# 408_jetracer_ledappend_board.net
KiCad netlist of a schematic drawn in EAGLE
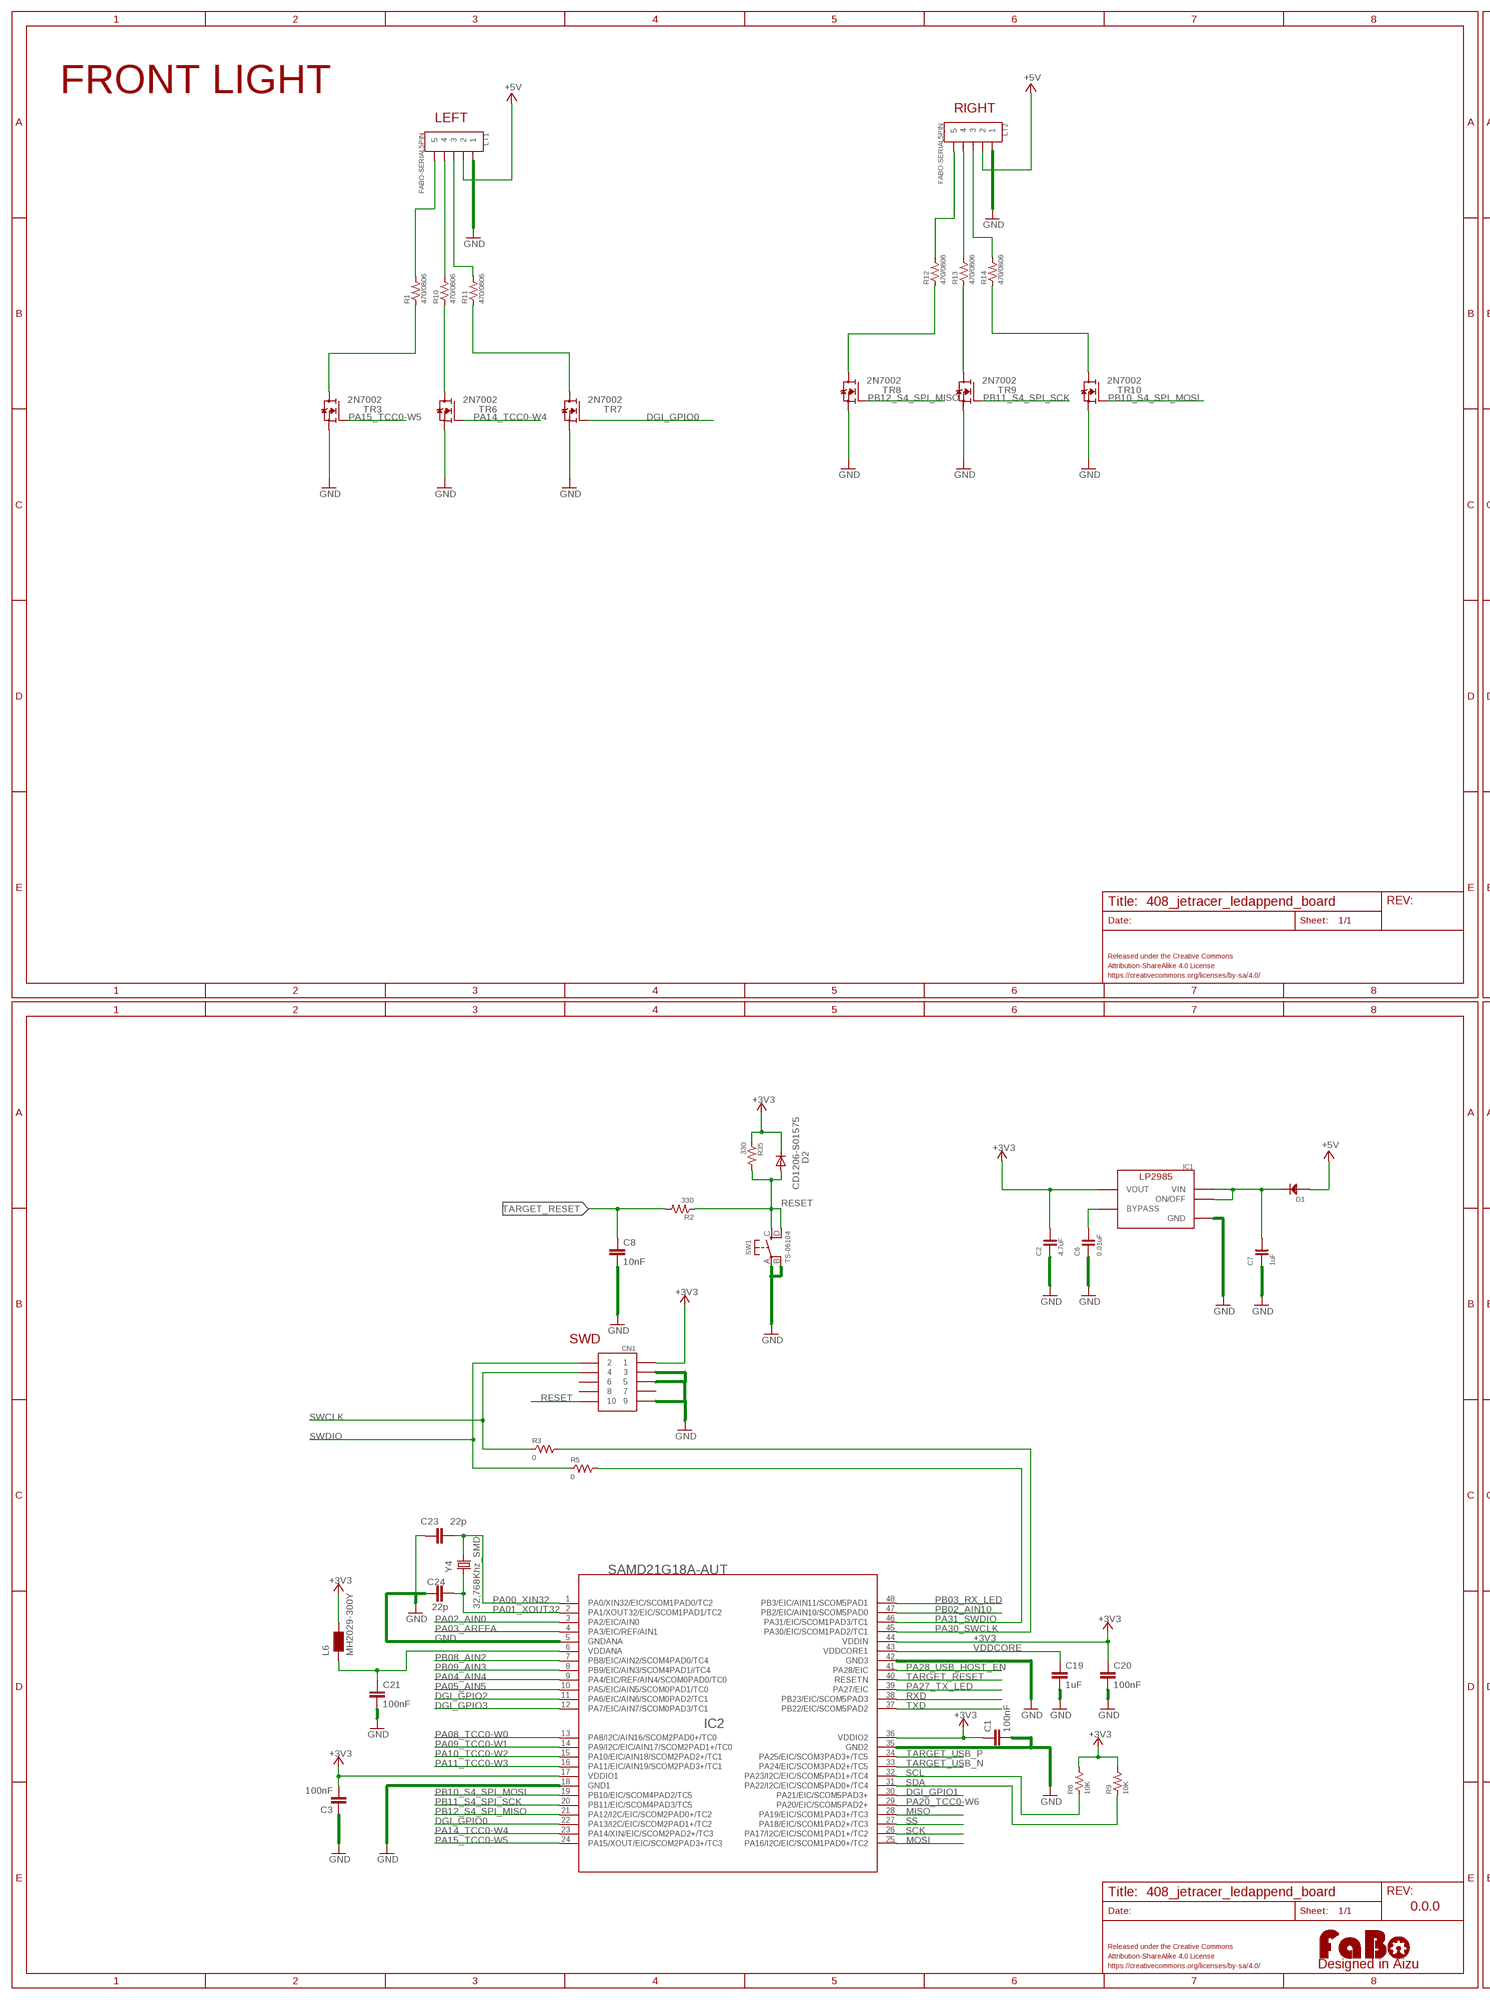
[diagram p0: schematic, sheet 1, part 1 of 2]
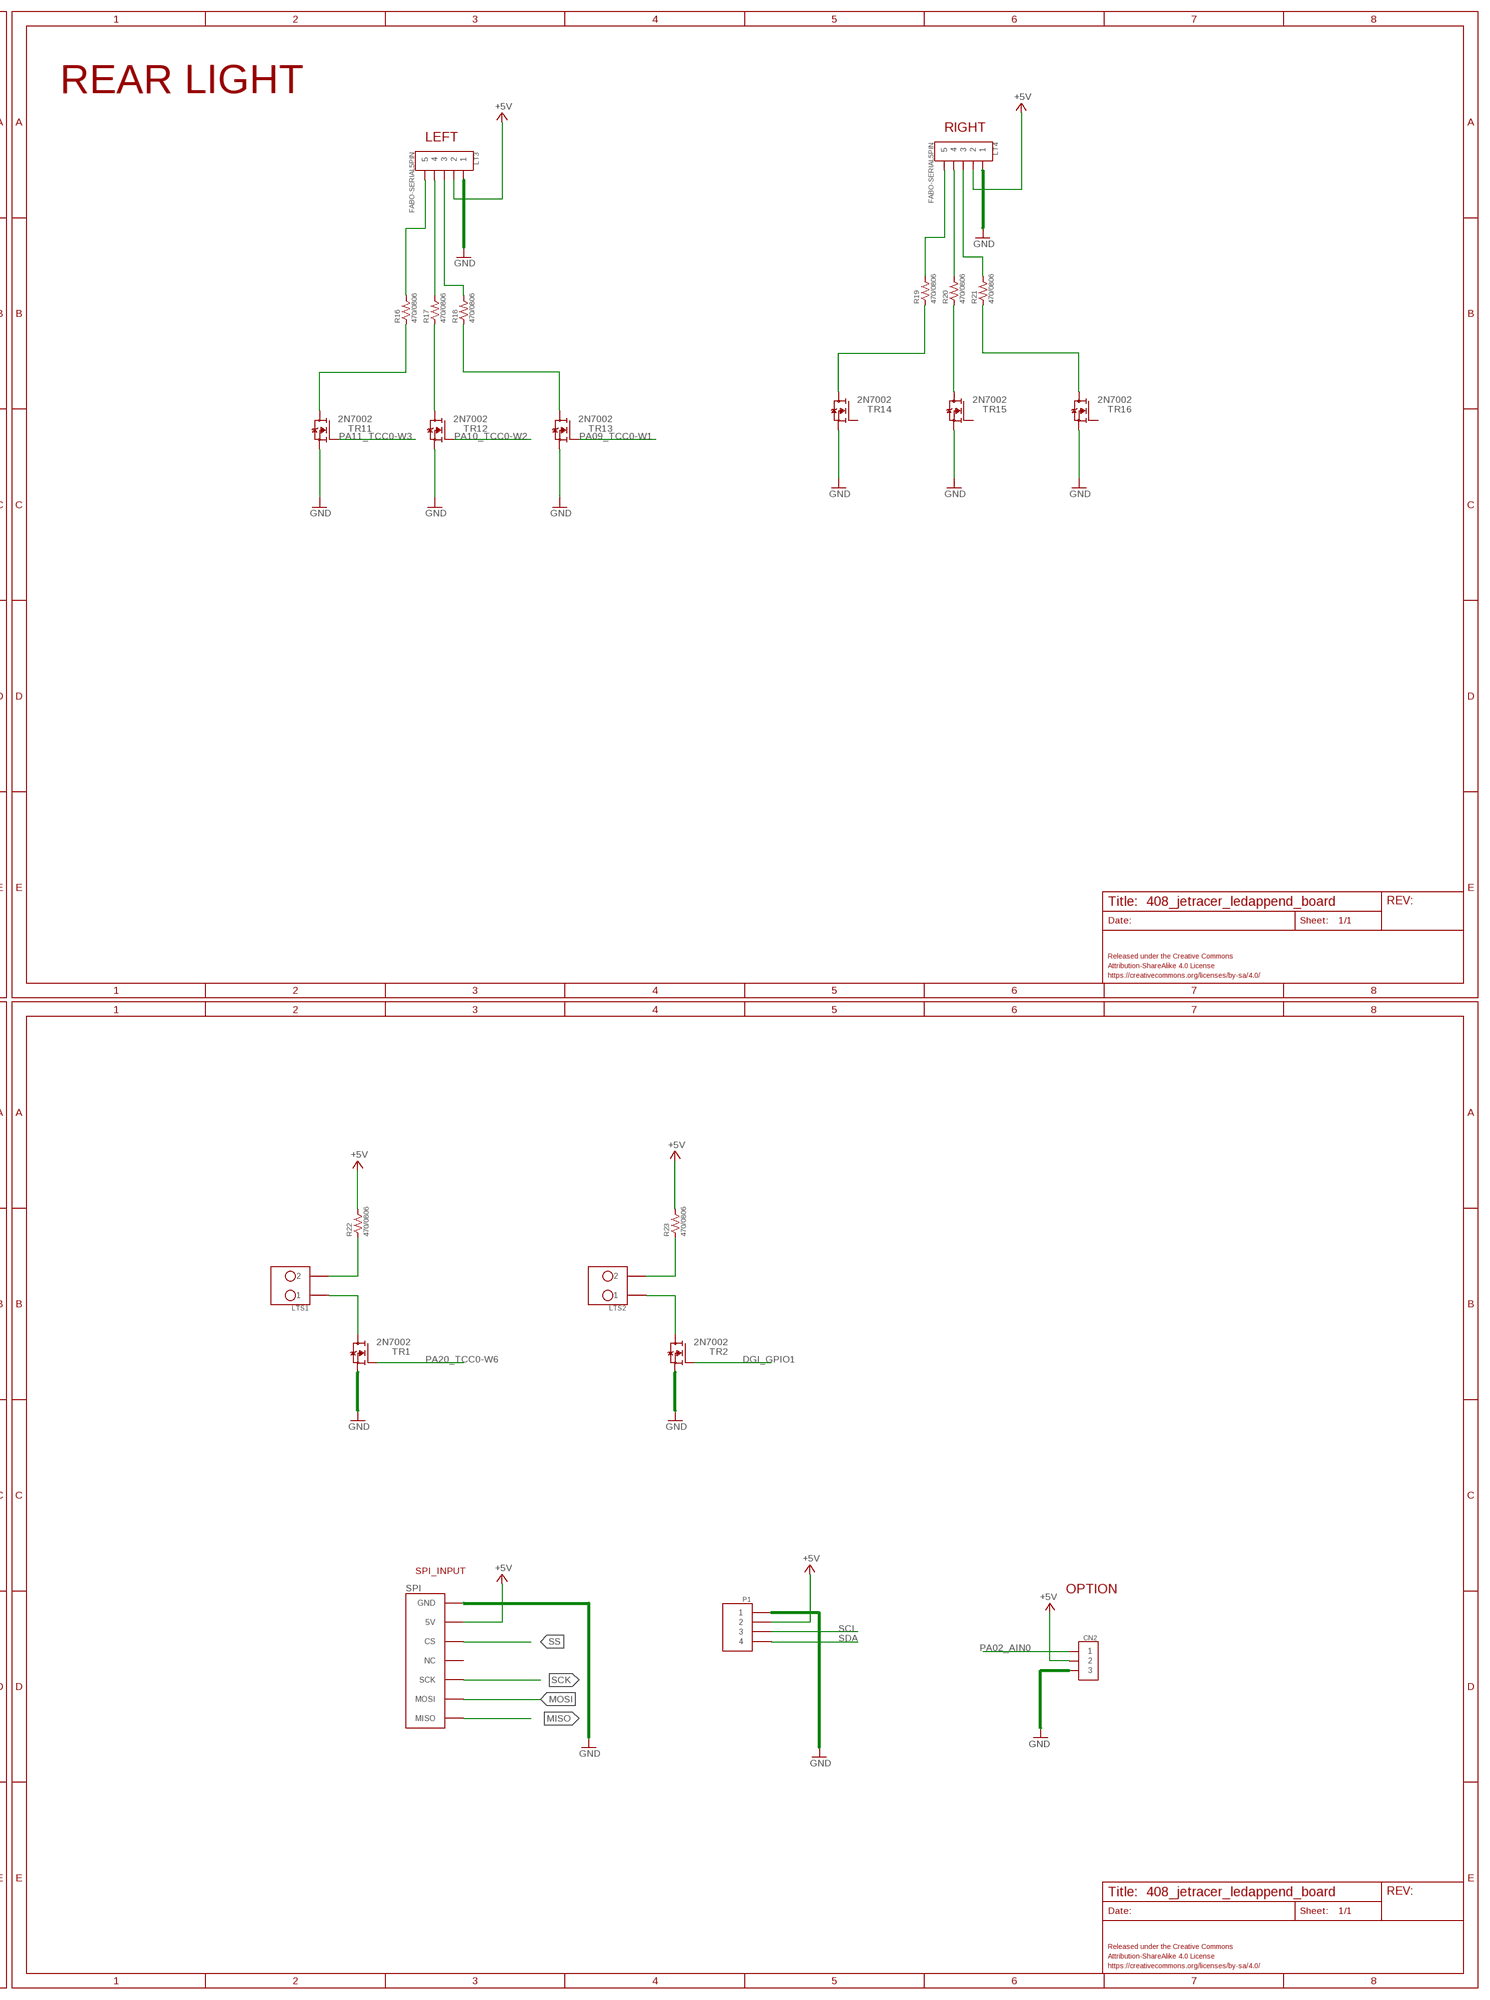
[diagram p1: schematic, sheet 1, part 2 of 2]

(export (version "E")
  (design (tool "Eeschema 10.0.6"))
  (components
    (comp (ref "C1")
      (value "100nF")
      (footprint "eagle-import:C0603-ROUND")
      (fields (field (name "PART_NUMBER") "cl10b104kbnc"))
      (libsource (lib "eagle-import") (part "0015_100NF_0603"))
    )
    (comp (ref "C2")
      (value "4.7uF")
      (footprint "eagle-import:0603")
      (libsource (lib "eagle-import") (part "CAPACITOR-0603"))
    )
    (comp (ref "C3")
      (value "100nF")
      (footprint "eagle-import:C0603-ROUND")
      (fields (field (name "PART_NUMBER") "cl10b104kbnc"))
      (libsource (lib "eagle-import") (part "0015_100NF_0603"))
    )
    (comp (ref "C6")
      (value "0.01uF")
      (footprint "eagle-import:0603")
      (libsource (lib "eagle-import") (part "CAPACITOR-0603"))
    )
    (comp (ref "C7")
      (value "1uF")
      (footprint "eagle-import:0603")
      (libsource (lib "eagle-import") (part "CAPACITOR-0603"))
    )
    (comp (ref "C8")
      (value "10nF")
      (footprint "eagle-import:C0603-ROUND")
      (fields (field (name "PART_NUMBER") "10nF_0603"))
      (libsource (lib "eagle-import") (part "0142_10NF_0603"))
    )
    (comp (ref "C19")
      (value "1uF")
      (footprint "eagle-import:C0603-ROUND")
      (fields (field (name "PART_NUMBER") "1uF_0603/GRM188R61E105KA12D"))
      (libsource (lib "eagle-import") (part "0006_1UF_0603/GRM188R61E105KA12D"))
    )
    (comp (ref "C20")
      (value "100nF")
      (footprint "eagle-import:C0603-ROUND")
      (fields (field (name "PART_NUMBER") "cl10b104kbnc"))
      (libsource (lib "eagle-import") (part "0015_100NF_0603"))
    )
    (comp (ref "C21")
      (value "100nF")
      (footprint "eagle-import:C0603-ROUND")
      (fields (field (name "PART_NUMBER") "cl10b104kbnc"))
      (libsource (lib "eagle-import") (part "0015_100NF_0603"))
    )
    (comp (ref "C23")
      (value "22p")
      (footprint "eagle-import:C0603-ROUND")
      (fields (field (name "PART_NUMBER") "22pF_0603"))
      (libsource (lib "eagle-import") (part "0014_22PF_0603"))
    )
    (comp (ref "C24")
      (value "22p")
      (footprint "eagle-import:C0603-ROUND")
      (fields (field (name "PART_NUMBER") "22pF_0603"))
      (libsource (lib "eagle-import") (part "0014_22PF_0603"))
    )
    (comp (ref "CN1")
      (value "PIN-HEADER-SMT(1.27MM)2X5")
      (footprint "eagle-import:PIN-HEADER-SMT(1.27MM)2X5")
      (libsource (lib "eagle-import") (part "PIN-HEADER-SMT(1.27MM)2X5"))
    )
    (comp (ref "CN2")
      (value "PIN_1X3")
      (footprint "eagle-import:PIN_1X3")
      (libsource (lib "eagle-import") (part "PIN_1X3"))
    )
    (comp (ref "D1")
      (value "DIODE-SOD-323")
      (footprint "eagle-import:SOD-323")
      (libsource (lib "eagle-import") (part "DIODE-SOD-323"))
    )
    (comp (ref "D2")
      (value "CD1206-S01575")
      (footprint "eagle-import:MINIMELF")
      (libsource (lib "eagle-import") (part "0012_CD1206-S01575"))
    )
    (comp (ref "IC1")
      (value "LP2985-33DBV")
      (footprint "eagle-import:SOT-23-5")
      (libsource (lib "eagle-import") (part "LP2985-33DBV"))
    )
    (comp (ref "IC2")
      (value "SAMD21G18A-AUT")
      (footprint "eagle-import:TQFP48-7X7")
      (libsource (lib "eagle-import") (part "1792_SAMD21G18A-AUT"))
    )
    (comp (ref "L6")
      (value "MH2029-300Y")
      (footprint "eagle-import:0805")
      (fields (field (name "PART_NUMBER") "BLM21PG300SN1D_/_MH2029-300Y"))
      (libsource (lib "eagle-import") (part "0001_BLM21PG300SN1D_/_MH2029-300Y"))
    )
    (comp (ref "LOGO2")
      (value "LOGO_FABO-M_BOTTOM")
      (footprint "eagle-import:LOGO_FABO_M_BOTTOM")
      (libsource (lib "eagle-import") (part "LOGO_FABO-M_BOTTOM"))
    )
    (comp (ref "LT1")
      (value "FABO-SERIAL5PIN")
      (footprint "eagle-import:BM05B-PASS-1")
      (libsource (lib "eagle-import") (part "FABO-SERIAL5PIN"))
    )
    (comp (ref "LT2")
      (value "FABO-SERIAL5PIN")
      (footprint "eagle-import:BM05B-PASS-1")
      (libsource (lib "eagle-import") (part "FABO-SERIAL5PIN"))
    )
    (comp (ref "LT3")
      (value "FABO-SERIAL5PIN")
      (footprint "eagle-import:BM05B-PASS-1")
      (libsource (lib "eagle-import") (part "FABO-SERIAL5PIN"))
    )
    (comp (ref "LT4")
      (value "FABO-SERIAL5PIN")
      (footprint "eagle-import:BM05B-PASS-1")
      (libsource (lib "eagle-import") (part "FABO-SERIAL5PIN"))
    )
    (comp (ref "LTS1")
      (value "B2B-XH-AM")
      (footprint "eagle-import:B2B-XH-AM")
      (libsource (lib "eagle-import") (part "B2B-XH-AM"))
    )
    (comp (ref "LTS2")
      (value "B2B-XH-AM")
      (footprint "eagle-import:B2B-XH-AM")
      (libsource (lib "eagle-import") (part "B2B-XH-AM"))
    )
    (comp (ref "P1")
      (value "4PIN_HEADER_1.25MM")
      (footprint "eagle-import:4PIN_1.25MM")
      (libsource (lib "eagle-import") (part "4PIN_HEADER_1.25MM"))
    )
    (comp (ref "R1")
      (value "470/0806")
      (footprint "eagle-import:0805")
      (libsource (lib "eagle-import") (part "RESISTOR-0805"))
    )
    (comp (ref "R2")
      (value "330")
      (footprint "eagle-import:0603")
      (libsource (lib "eagle-import") (part "RESISTOR-0603"))
    )
    (comp (ref "R3")
      (value "0")
      (footprint "eagle-import:0603")
      (libsource (lib "eagle-import") (part "RESISTOR-0603"))
    )
    (comp (ref "R5")
      (value "0")
      (footprint "eagle-import:0603")
      (libsource (lib "eagle-import") (part "RESISTOR-0603"))
    )
    (comp (ref "R8")
      (value "10K")
      (footprint "eagle-import:0603")
      (libsource (lib "eagle-import") (part "RESISTOR-0603"))
    )
    (comp (ref "R9")
      (value "10K")
      (footprint "eagle-import:0603")
      (libsource (lib "eagle-import") (part "RESISTOR-0603"))
    )
    (comp (ref "R10")
      (value "470/0806")
      (footprint "eagle-import:0805")
      (libsource (lib "eagle-import") (part "RESISTOR-0805"))
    )
    (comp (ref "R11")
      (value "470/0806")
      (footprint "eagle-import:0805")
      (libsource (lib "eagle-import") (part "RESISTOR-0805"))
    )
    (comp (ref "R12")
      (value "470/0806")
      (footprint "eagle-import:0805")
      (libsource (lib "eagle-import") (part "RESISTOR-0805"))
    )
    (comp (ref "R13")
      (value "470/0806")
      (footprint "eagle-import:0805")
      (libsource (lib "eagle-import") (part "RESISTOR-0805"))
    )
    (comp (ref "R14")
      (value "470/0806")
      (footprint "eagle-import:0805")
      (libsource (lib "eagle-import") (part "RESISTOR-0805"))
    )
    (comp (ref "R16")
      (value "470/0806")
      (footprint "eagle-import:0805")
      (libsource (lib "eagle-import") (part "RESISTOR-0805"))
    )
    (comp (ref "R17")
      (value "470/0806")
      (footprint "eagle-import:0805")
      (libsource (lib "eagle-import") (part "RESISTOR-0805"))
    )
    (comp (ref "R18")
      (value "470/0806")
      (footprint "eagle-import:0805")
      (libsource (lib "eagle-import") (part "RESISTOR-0805"))
    )
    (comp (ref "R19")
      (value "470/0806")
      (footprint "eagle-import:0805")
      (libsource (lib "eagle-import") (part "RESISTOR-0805"))
    )
    (comp (ref "R20")
      (value "470/0806")
      (footprint "eagle-import:0805")
      (libsource (lib "eagle-import") (part "RESISTOR-0805"))
    )
    (comp (ref "R21")
      (value "470/0806")
      (footprint "eagle-import:0805")
      (libsource (lib "eagle-import") (part "RESISTOR-0805"))
    )
    (comp (ref "R22")
      (value "470/0806")
      (footprint "eagle-import:0805")
      (libsource (lib "eagle-import") (part "RESISTOR-0805"))
    )
    (comp (ref "R23")
      (value "470/0806")
      (footprint "eagle-import:0805")
      (libsource (lib "eagle-import") (part "RESISTOR-0805"))
    )
    (comp (ref "R35")
      (value "330")
      (footprint "eagle-import:0603")
      (libsource (lib "eagle-import") (part "RESISTOR-0603"))
    )
    (comp (ref "SPI")
      (value "FABO-7PINMULTI_SPI")
      (footprint "eagle-import:BM07B-PASS-1")
      (libsource (lib "eagle-import") (part "FABO-7PINMULTI_SPI"))
    )
    (comp (ref "SW1")
      (value "TS-06104")
      (footprint "eagle-import:TS-06104")
      (libsource (lib "eagle-import") (part "TS-06104"))
    )
    (comp (ref "TR1")
      (value "2N7002")
      (footprint "eagle-import:SOT-23")
      (libsource (lib "eagle-import") (part "1612_2N7002LT1G"))
    )
    (comp (ref "TR2")
      (value "2N7002")
      (footprint "eagle-import:SOT-23")
      (libsource (lib "eagle-import") (part "1612_2N7002LT1G"))
    )
    (comp (ref "TR3")
      (value "2N7002")
      (footprint "eagle-import:SOT-23")
      (libsource (lib "eagle-import") (part "1612_2N7002LT1G"))
    )
    (comp (ref "TR6")
      (value "2N7002")
      (footprint "eagle-import:SOT-23")
      (libsource (lib "eagle-import") (part "1612_2N7002LT1G"))
    )
    (comp (ref "TR7")
      (value "2N7002")
      (footprint "eagle-import:SOT-23")
      (libsource (lib "eagle-import") (part "1612_2N7002LT1G"))
    )
    (comp (ref "TR8")
      (value "2N7002")
      (footprint "eagle-import:SOT-23")
      (libsource (lib "eagle-import") (part "1612_2N7002LT1G"))
    )
    (comp (ref "TR9")
      (value "2N7002")
      (footprint "eagle-import:SOT-23")
      (libsource (lib "eagle-import") (part "1612_2N7002LT1G"))
    )
    (comp (ref "TR10")
      (value "2N7002")
      (footprint "eagle-import:SOT-23")
      (libsource (lib "eagle-import") (part "1612_2N7002LT1G"))
    )
    (comp (ref "TR11")
      (value "2N7002")
      (footprint "eagle-import:SOT-23")
      (libsource (lib "eagle-import") (part "1612_2N7002LT1G"))
    )
    (comp (ref "TR12")
      (value "2N7002")
      (footprint "eagle-import:SOT-23")
      (libsource (lib "eagle-import") (part "1612_2N7002LT1G"))
    )
    (comp (ref "TR13")
      (value "2N7002")
      (footprint "eagle-import:SOT-23")
      (libsource (lib "eagle-import") (part "1612_2N7002LT1G"))
    )
    (comp (ref "TR14")
      (value "2N7002")
      (footprint "eagle-import:SOT-23")
      (libsource (lib "eagle-import") (part "1612_2N7002LT1G"))
    )
    (comp (ref "TR15")
      (value "2N7002")
      (footprint "eagle-import:SOT-23")
      (libsource (lib "eagle-import") (part "1612_2N7002LT1G"))
    )
    (comp (ref "TR16")
      (value "2N7002")
      (footprint "eagle-import:SOT-23")
      (libsource (lib "eagle-import") (part "1612_2N7002LT1G"))
    )
    (comp (ref "Y4")
      (value "32,768Khz_SMD")
      (footprint "eagle-import:RESONATOR_EPSON_FC_145")
      (fields (field (name "PART_NUMBER") "ABS07-32.768KHZ-T"))
      (libsource (lib "eagle-import") (part "0213_ABS07-32.768KHZ-T"))
    )
  )
  (nets
    (net (code "1") (name "+3V3") (class "Default")
      (node (ref "C1") (pin "1") (pinfunction "1_1") (pintype "passive"))
      (node (ref "C2") (pin "2") (pinfunction "2_2") (pintype "passive"))
      (node (ref "C20") (pin "1") (pinfunction "1_1") (pintype "passive"))
      (node (ref "C3") (pin "2") (pinfunction "2_2") (pintype "passive"))
      (node (ref "CN1") (pin "1") (pinfunction "1_1") (pintype "bidirectional"))
      (node (ref "D2") (pin "C") (pinfunction "C_C") (pintype "passive"))
      (node (ref "IC1") (pin "5") (pinfunction "VOUT_5") (pintype "output"))
      (node (ref "IC2") (pin "17") (pinfunction "VDDIO1_17") (pintype "power_in"))
      (node (ref "IC2") (pin "36") (pinfunction "VDDIO2_36") (pintype "power_in"))
      (node (ref "IC2") (pin "44") (pinfunction "VDDIN_44") (pintype "power_in"))
      (node (ref "L6") (pin "2") (pinfunction "2_2") (pintype "passive"))
      (node (ref "R35") (pin "1") (pinfunction "1_1") (pintype "bidirectional"))
      (node (ref "R8") (pin "2") (pinfunction "2_2") (pintype "bidirectional"))
      (node (ref "R9") (pin "2") (pinfunction "2_2") (pintype "bidirectional"))
    )
    (net (code "2") (name "+5V") (class "Default")
      (node (ref "CN2") (pin "2") (pinfunction "2_2") (pintype "bidirectional"))
      (node (ref "D1") (pin "A") (pinfunction "ANODE_A") (pintype "bidirectional"))
      (node (ref "LT1") (pin "2") (pinfunction "2_2") (pintype "bidirectional"))
      (node (ref "LT2") (pin "2") (pinfunction "2_2") (pintype "bidirectional"))
      (node (ref "LT3") (pin "2") (pinfunction "2_2") (pintype "bidirectional"))
      (node (ref "LT4") (pin "2") (pinfunction "2_2") (pintype "bidirectional"))
      (node (ref "P1") (pin "2") (pinfunction "2_2") (pintype "bidirectional"))
      (node (ref "R22") (pin "2") (pinfunction "2_2") (pintype "bidirectional"))
      (node (ref "R23") (pin "2") (pinfunction "2_2") (pintype "bidirectional"))
      (node (ref "SPI") (pin "2") (pinfunction "5V_2") (pintype "bidirectional"))
    )
    (net (code "3") (name "/DGI_GPIO0") (class "Default")
      (node (ref "IC2") (pin "22") (pinfunction "PA13/I2C/EIC/SCOM2PAD1+/TC2_22") (pintype "bidirectional"))
      (node (ref "TR7") (pin "3") (pinfunction "G_3") (pintype "passive"))
    )
    (net (code "4") (name "/DGI_GPIO1") (class "Default")
      (node (ref "IC2") (pin "30") (pinfunction "PA21/EIC/SCOM5PAD3+_30") (pintype "bidirectional"))
      (node (ref "TR2") (pin "3") (pinfunction "G_3") (pintype "passive"))
    )
    (net (code "5") (name "/DGI_GPIO2") (class "Default")
      (node (ref "IC2") (pin "11") (pinfunction "PA6/EIC/AIN6/SCOM0PAD2/TC1_11") (pintype "bidirectional"))
    )
    (net (code "6") (name "/DGI_GPIO3") (class "Default")
      (node (ref "IC2") (pin "12") (pinfunction "PA7/EIC/AIN7/SCOM0PAD3/TC1_12") (pintype "bidirectional"))
    )
    (net (code "7") (name "/PA00_XIN32") (class "Default")
      (node (ref "C23") (pin "2") (pinfunction "2_2") (pintype "passive"))
      (node (ref "IC2") (pin "1") (pinfunction "PA0/XIN32/EIC/SCOM1PAD0/TC2_1") (pintype "bidirectional"))
      (node (ref "Y4") (pin "P$2") (pinfunction "2_P$2") (pintype "bidirectional"))
    )
    (net (code "8") (name "/PA01_XOUT32") (class "Default")
      (node (ref "C24") (pin "2") (pinfunction "2_2") (pintype "passive"))
      (node (ref "IC2") (pin "2") (pinfunction "PA1/XOUT32/EIC/SCOM1PAD1/TC2_2") (pintype "bidirectional"))
      (node (ref "Y4") (pin "P$1") (pinfunction "1_P$1") (pintype "bidirectional"))
    )
    (net (code "9") (name "/PA02_AIN0") (class "Default")
      (node (ref "CN2") (pin "1") (pinfunction "1_1") (pintype "bidirectional"))
      (node (ref "IC2") (pin "3") (pinfunction "PA2/EIC/AIN0_3") (pintype "bidirectional"))
    )
    (net (code "10") (name "/PA03_AREFA") (class "Default")
      (node (ref "IC2") (pin "4") (pinfunction "PA3/EIC/REF/AIN1_4") (pintype "bidirectional"))
    )
    (net (code "11") (name "/PA04_AIN4") (class "Default")
      (node (ref "IC2") (pin "9") (pinfunction "PA4/EIC/REF/AIN4/SCOM0PAD0/TC0_9") (pintype "bidirectional"))
    )
    (net (code "12") (name "/PA05_AIN5") (class "Default")
      (node (ref "IC2") (pin "10") (pinfunction "PA5/EIC/AIN5/SCOM0PAD1/TC0_10") (pintype "bidirectional"))
    )
    (net (code "13") (name "/PA08_TCC0-W0") (class "Default")
      (node (ref "IC2") (pin "13") (pinfunction "PA8/I2C/AIN16/SCOM2PAD0+/TC0_13") (pintype "bidirectional"))
    )
    (net (code "14") (name "/PA09_TCC0-W1") (class "Default")
      (node (ref "IC2") (pin "14") (pinfunction "PA9/I2C/EIC/AIN17/SCOM2PAD1+/TC0_14") (pintype "bidirectional"))
      (node (ref "TR13") (pin "3") (pinfunction "G_3") (pintype "passive"))
    )
    (net (code "15") (name "/PA10_TCC0-W2") (class "Default")
      (node (ref "IC2") (pin "15") (pinfunction "PA10/EIC/AIN18/SCOM2PAD2+/TC1_15") (pintype "bidirectional"))
      (node (ref "TR12") (pin "3") (pinfunction "G_3") (pintype "passive"))
    )
    (net (code "16") (name "/PA11_TCC0-W3") (class "Default")
      (node (ref "IC2") (pin "16") (pinfunction "PA11/EIC/AIN19/SCOM2PAD3+/TC1_16") (pintype "bidirectional"))
      (node (ref "TR11") (pin "3") (pinfunction "G_3") (pintype "passive"))
    )
    (net (code "17") (name "/PA14_TCC0-W4") (class "Default")
      (node (ref "IC2") (pin "23") (pinfunction "PA14/XIN/EIC/SCOM2PAD2+/TC3_23") (pintype "bidirectional"))
      (node (ref "TR6") (pin "3") (pinfunction "G_3") (pintype "passive"))
    )
    (net (code "18") (name "/PA15_TCC0-W5") (class "Default")
      (node (ref "IC2") (pin "24") (pinfunction "PA15/XOUT/EIC/SCOM2PAD3+/TC3_24") (pintype "bidirectional"))
      (node (ref "TR3") (pin "3") (pinfunction "G_3") (pintype "passive"))
    )
    (net (code "19") (name "/PA20_TCC0-W6") (class "Default")
      (node (ref "IC2") (pin "29") (pinfunction "PA20/EIC/SCOM5PAD2+_29") (pintype "bidirectional"))
      (node (ref "TR1") (pin "3") (pinfunction "G_3") (pintype "passive"))
    )
    (net (code "20") (name "/PA27_TX_LED") (class "Default")
      (node (ref "IC2") (pin "39") (pinfunction "PA27/EIC_39") (pintype "bidirectional"))
    )
    (net (code "21") (name "/PA28_USB_HOST_EN") (class "Default")
      (node (ref "IC2") (pin "41") (pinfunction "PA28/EIC_41") (pintype "bidirectional"))
    )
    (net (code "22") (name "/PA30_SWCLK") (class "Default")
      (node (ref "IC2") (pin "45") (pinfunction "PA30/EIC/SCOM1PAD2/TC1_45") (pintype "bidirectional"))
      (node (ref "R3") (pin "2") (pinfunction "2_2") (pintype "bidirectional"))
    )
    (net (code "23") (name "/PA31_SWDIO") (class "Default")
      (node (ref "IC2") (pin "46") (pinfunction "PA31/EIC/SCOM1PAD3/TC1_46") (pintype "bidirectional"))
      (node (ref "R5") (pin "2") (pinfunction "2_2") (pintype "bidirectional"))
    )
    (net (code "24") (name "/PB02_AIN10") (class "Default")
      (node (ref "IC2") (pin "47") (pinfunction "PB2/EIC/AIN10/SCOM5PAD0_47") (pintype "bidirectional"))
    )
    (net (code "25") (name "/PB03_RX_LED") (class "Default")
      (node (ref "IC2") (pin "48") (pinfunction "PB3/EIC/AIN11/SCOM5PAD1_48") (pintype "bidirectional"))
    )
    (net (code "26") (name "/PB08_AIN2") (class "Default")
      (node (ref "IC2") (pin "7") (pinfunction "PB8/EIC/AIN2/SCOM4PAD0/TC4_7") (pintype "bidirectional"))
    )
    (net (code "27") (name "/PB09_AIN3") (class "Default")
      (node (ref "IC2") (pin "8") (pinfunction "PB9/EIC/AIN3/SCOM4PAD1//TC4_8") (pintype "bidirectional"))
    )
    (net (code "28") (name "/PB10_S4_SPI_MOSI") (class "Default")
      (node (ref "IC2") (pin "19") (pinfunction "PB10/EIC/SCOM4PAD2/TC5_19") (pintype "bidirectional"))
      (node (ref "TR10") (pin "3") (pinfunction "G_3") (pintype "passive"))
    )
    (net (code "29") (name "/PB11_S4_SPI_SCK") (class "Default")
      (node (ref "IC2") (pin "20") (pinfunction "PB11/EIC/SCOM4PAD3/TC5_20") (pintype "bidirectional"))
      (node (ref "TR9") (pin "3") (pinfunction "G_3") (pintype "passive"))
    )
    (net (code "30") (name "/PB12_S4_SPI_MISO") (class "Default")
      (node (ref "IC2") (pin "21") (pinfunction "PA12/I2C/EIC/SCOM2PAD0+/TC2_21") (pintype "bidirectional"))
      (node (ref "TR8") (pin "3") (pinfunction "G_3") (pintype "passive"))
    )
    (net (code "31") (name "/RESET") (class "Default")
      (node (ref "CN1") (pin "10") (pinfunction "10_10") (pintype "bidirectional"))
      (node (ref "D2") (pin "A") (pinfunction "A_A") (pintype "passive"))
      (node (ref "R2") (pin "1") (pinfunction "1_1") (pintype "bidirectional"))
      (node (ref "R35") (pin "2") (pinfunction "2_2") (pintype "bidirectional"))
      (node (ref "SW1") (pin "C") (pinfunction "C_C") (pintype "passive"))
      (node (ref "SW1") (pin "D") (pinfunction "D_D") (pintype "passive"))
    )
    (net (code "32") (name "/RXD") (class "Default")
      (node (ref "IC2") (pin "38") (pinfunction "PB23/EIC/SCOM5PAD3_38") (pintype "bidirectional"))
    )
    (net (code "33") (name "/SCL") (class "Default")
      (node (ref "IC2") (pin "32") (pinfunction "PA23/I2C/EIC/SCOM5PAD1+/TC4_32") (pintype "bidirectional"))
      (node (ref "P1") (pin "3") (pinfunction "3_3") (pintype "bidirectional"))
      (node (ref "R8") (pin "1") (pinfunction "1_1") (pintype "bidirectional"))
    )
    (net (code "34") (name "/SDA") (class "Default")
      (node (ref "IC2") (pin "31") (pinfunction "PA22/I2C/EIC/SCOM5PAD0+/TC4_31") (pintype "bidirectional"))
      (node (ref "P1") (pin "4") (pinfunction "4_4") (pintype "bidirectional"))
      (node (ref "R9") (pin "1") (pinfunction "1_1") (pintype "bidirectional"))
    )
    (net (code "35") (name "/SWCLK") (class "Default")
      (node (ref "CN1") (pin "4") (pinfunction "4_4") (pintype "bidirectional"))
      (node (ref "R3") (pin "1") (pinfunction "1_1") (pintype "bidirectional"))
    )
    (net (code "36") (name "/SWDIO") (class "Default")
      (node (ref "CN1") (pin "2") (pinfunction "2_2") (pintype "bidirectional"))
      (node (ref "R5") (pin "1") (pinfunction "1_1") (pintype "bidirectional"))
    )
    (net (code "37") (name "/TARGET_USB_N") (class "Default")
      (node (ref "IC2") (pin "33") (pinfunction "PA24/EIC/SCOM3PAD2+/TC5_33") (pintype "bidirectional"))
    )
    (net (code "38") (name "/TARGET_USB_P") (class "Default")
      (node (ref "IC2") (pin "34") (pinfunction "PA25/EIC/SCOM3PAD3+/TC5_34") (pintype "bidirectional"))
    )
    (net (code "39") (name "/TXD") (class "Default")
      (node (ref "IC2") (pin "37") (pinfunction "PB22/EIC/SCOM5PAD2_37") (pintype "bidirectional"))
    )
    (net (code "40") (name "/VDDCORE") (class "Default")
      (node (ref "C19") (pin "1") (pinfunction "1_1") (pintype "passive"))
      (node (ref "IC2") (pin "43") (pinfunction "VDDCORE1_43") (pintype "input"))
    )
    (net (code "41") (name "GND") (class "Default")
      (node (ref "C1") (pin "2") (pinfunction "2_2") (pintype "passive"))
      (node (ref "C19") (pin "2") (pinfunction "2_2") (pintype "passive"))
      (node (ref "C2") (pin "1") (pinfunction "1_1") (pintype "passive"))
      (node (ref "C20") (pin "2") (pinfunction "2_2") (pintype "passive"))
      (node (ref "C21") (pin "2") (pinfunction "2_2") (pintype "passive"))
      (node (ref "C23") (pin "1") (pinfunction "1_1") (pintype "passive"))
      (node (ref "C24") (pin "1") (pinfunction "1_1") (pintype "passive"))
      (node (ref "C3") (pin "1") (pinfunction "1_1") (pintype "passive"))
      (node (ref "C6") (pin "1") (pinfunction "1_1") (pintype "passive"))
      (node (ref "C7") (pin "1") (pinfunction "1_1") (pintype "passive"))
      (node (ref "C8") (pin "2") (pinfunction "2_2") (pintype "passive"))
      (node (ref "CN1") (pin "3") (pinfunction "3_3") (pintype "bidirectional"))
      (node (ref "CN1") (pin "5") (pinfunction "5_5") (pintype "bidirectional"))
      (node (ref "CN1") (pin "9") (pinfunction "9_9") (pintype "bidirectional"))
      (node (ref "CN2") (pin "3") (pinfunction "3_3") (pintype "bidirectional"))
      (node (ref "IC1") (pin "2") (pinfunction "GND_2") (pintype "power_in"))
      (node (ref "IC2") (pin "18") (pinfunction "GND1_18") (pintype "power_in"))
      (node (ref "IC2") (pin "35") (pinfunction "GND2_35") (pintype "power_in"))
      (node (ref "IC2") (pin "42") (pinfunction "GND3_42") (pintype "power_in"))
      (node (ref "IC2") (pin "5") (pinfunction "GNDANA_5") (pintype "power_in"))
      (node (ref "LT1") (pin "1") (pinfunction "1_1") (pintype "bidirectional"))
      (node (ref "LT2") (pin "1") (pinfunction "1_1") (pintype "bidirectional"))
      (node (ref "LT3") (pin "1") (pinfunction "1_1") (pintype "bidirectional"))
      (node (ref "LT4") (pin "1") (pinfunction "1_1") (pintype "bidirectional"))
      (node (ref "P1") (pin "1") (pinfunction "1_1") (pintype "bidirectional"))
      (node (ref "SPI") (pin "1") (pinfunction "GND_1") (pintype "bidirectional"))
      (node (ref "SW1") (pin "A") (pinfunction "A_A") (pintype "passive"))
      (node (ref "SW1") (pin "B") (pinfunction "B_B") (pintype "passive"))
      (node (ref "TR1") (pin "2") (pinfunction "S_2") (pintype "passive"))
      (node (ref "TR10") (pin "2") (pinfunction "S_2") (pintype "passive"))
      (node (ref "TR11") (pin "2") (pinfunction "S_2") (pintype "passive"))
      (node (ref "TR12") (pin "2") (pinfunction "S_2") (pintype "passive"))
      (node (ref "TR13") (pin "2") (pinfunction "S_2") (pintype "passive"))
      (node (ref "TR14") (pin "2") (pinfunction "S_2") (pintype "passive"))
      (node (ref "TR15") (pin "2") (pinfunction "S_2") (pintype "passive"))
      (node (ref "TR16") (pin "2") (pinfunction "S_2") (pintype "passive"))
      (node (ref "TR2") (pin "2") (pinfunction "S_2") (pintype "passive"))
      (node (ref "TR3") (pin "2") (pinfunction "S_2") (pintype "passive"))
      (node (ref "TR6") (pin "2") (pinfunction "S_2") (pintype "passive"))
      (node (ref "TR7") (pin "2") (pinfunction "S_2") (pintype "passive"))
      (node (ref "TR8") (pin "2") (pinfunction "S_2") (pintype "passive"))
      (node (ref "TR9") (pin "2") (pinfunction "S_2") (pintype "passive"))
    )
    (net (code "42") (name "MISO") (class "Default")
      (node (ref "IC2") (pin "28") (pinfunction "PA19/EIC/SCOM1PAD3+/TC3_28") (pintype "bidirectional"))
      (node (ref "SPI") (pin "7") (pinfunction "MISO_7") (pintype "bidirectional"))
    )
    (net (code "43") (name "MOSI") (class "Default")
      (node (ref "IC2") (pin "25") (pinfunction "PA16/I2C/EIC/SCOM1PAD0+/TC2_25") (pintype "bidirectional"))
      (node (ref "SPI") (pin "6") (pinfunction "MOSI_6") (pintype "bidirectional"))
    )
    (net (code "44") (name "Net-(D1-CATHODE)") (class "Default")
      (node (ref "C7") (pin "2") (pinfunction "2_2") (pintype "passive"))
      (node (ref "D1") (pin "K") (pinfunction "CATHODE_K") (pintype "bidirectional"))
      (node (ref "IC1") (pin "1") (pinfunction "VIN_1") (pintype "input"))
      (node (ref "IC1") (pin "3") (pinfunction "ON/OFF_3") (pintype "input"))
    )
    (net (code "45") (name "Net-(IC1-BYPASS)") (class "Default")
      (node (ref "C6") (pin "2") (pinfunction "2_2") (pintype "passive"))
      (node (ref "IC1") (pin "4") (pinfunction "BYPASS_4") (pintype "bidirectional"))
    )
    (net (code "46") (name "Net-(IC2-VDDANA)") (class "Default")
      (node (ref "C21") (pin "1") (pinfunction "1_1") (pintype "passive"))
      (node (ref "IC2") (pin "6") (pinfunction "VDDANA_6") (pintype "power_in"))
      (node (ref "L6") (pin "1") (pinfunction "1_1") (pintype "passive"))
    )
    (net (code "47") (name "Net-(LT1-Pad3)") (class "Default")
      (node (ref "LT1") (pin "3") (pinfunction "3_3") (pintype "bidirectional"))
      (node (ref "R11") (pin "2") (pinfunction "2_2") (pintype "bidirectional"))
    )
    (net (code "48") (name "Net-(LT1-Pad4)") (class "Default")
      (node (ref "LT1") (pin "4") (pinfunction "4_4") (pintype "bidirectional"))
      (node (ref "R10") (pin "2") (pinfunction "2_2") (pintype "bidirectional"))
    )
    (net (code "49") (name "Net-(LT1-Pad5)") (class "Default")
      (node (ref "LT1") (pin "5") (pinfunction "5_5") (pintype "bidirectional"))
      (node (ref "R1") (pin "2") (pinfunction "2_2") (pintype "bidirectional"))
    )
    (net (code "50") (name "Net-(LT2-Pad3)") (class "Default")
      (node (ref "LT2") (pin "3") (pinfunction "3_3") (pintype "bidirectional"))
      (node (ref "R14") (pin "2") (pinfunction "2_2") (pintype "bidirectional"))
    )
    (net (code "51") (name "Net-(LT2-Pad4)") (class "Default")
      (node (ref "LT2") (pin "4") (pinfunction "4_4") (pintype "bidirectional"))
      (node (ref "R13") (pin "2") (pinfunction "2_2") (pintype "bidirectional"))
    )
    (net (code "52") (name "Net-(LT2-Pad5)") (class "Default")
      (node (ref "LT2") (pin "5") (pinfunction "5_5") (pintype "bidirectional"))
      (node (ref "R12") (pin "2") (pinfunction "2_2") (pintype "bidirectional"))
    )
    (net (code "53") (name "Net-(LT3-Pad3)") (class "Default")
      (node (ref "LT3") (pin "3") (pinfunction "3_3") (pintype "bidirectional"))
      (node (ref "R18") (pin "2") (pinfunction "2_2") (pintype "bidirectional"))
    )
    (net (code "54") (name "Net-(LT3-Pad4)") (class "Default")
      (node (ref "LT3") (pin "4") (pinfunction "4_4") (pintype "bidirectional"))
      (node (ref "R17") (pin "2") (pinfunction "2_2") (pintype "bidirectional"))
    )
    (net (code "55") (name "Net-(LT3-Pad5)") (class "Default")
      (node (ref "LT3") (pin "5") (pinfunction "5_5") (pintype "bidirectional"))
      (node (ref "R16") (pin "2") (pinfunction "2_2") (pintype "bidirectional"))
    )
    (net (code "56") (name "Net-(LT4-Pad3)") (class "Default")
      (node (ref "LT4") (pin "3") (pinfunction "3_3") (pintype "bidirectional"))
      (node (ref "R21") (pin "2") (pinfunction "2_2") (pintype "bidirectional"))
    )
    (net (code "57") (name "Net-(LT4-Pad4)") (class "Default")
      (node (ref "LT4") (pin "4") (pinfunction "4_4") (pintype "bidirectional"))
      (node (ref "R20") (pin "2") (pinfunction "2_2") (pintype "bidirectional"))
    )
    (net (code "58") (name "Net-(LT4-Pad5)") (class "Default")
      (node (ref "LT4") (pin "5") (pinfunction "5_5") (pintype "bidirectional"))
      (node (ref "R19") (pin "2") (pinfunction "2_2") (pintype "bidirectional"))
    )
    (net (code "59") (name "Net-(LTS1-Pad2)") (class "Default")
      (node (ref "LTS1") (pin "2") (pinfunction "2_2") (pintype "bidirectional"))
      (node (ref "R22") (pin "1") (pinfunction "1_1") (pintype "bidirectional"))
    )
    (net (code "60") (name "Net-(LTS2-Pad2)") (class "Default")
      (node (ref "LTS2") (pin "2") (pinfunction "2_2") (pintype "bidirectional"))
      (node (ref "R23") (pin "1") (pinfunction "1_1") (pintype "bidirectional"))
    )
    (net (code "61") (name "Net-(TR1-D)") (class "Default")
      (node (ref "LTS1") (pin "1") (pinfunction "1_1") (pintype "bidirectional"))
      (node (ref "TR1") (pin "1") (pinfunction "D_1") (pintype "passive"))
    )
    (net (code "62") (name "Net-(TR2-D)") (class "Default")
      (node (ref "LTS2") (pin "1") (pinfunction "1_1") (pintype "bidirectional"))
      (node (ref "TR2") (pin "1") (pinfunction "D_1") (pintype "passive"))
    )
    (net (code "63") (name "Net-(TR3-D)") (class "Default")
      (node (ref "R1") (pin "1") (pinfunction "1_1") (pintype "bidirectional"))
      (node (ref "TR3") (pin "1") (pinfunction "D_1") (pintype "passive"))
    )
    (net (code "64") (name "Net-(TR6-D)") (class "Default")
      (node (ref "R10") (pin "1") (pinfunction "1_1") (pintype "bidirectional"))
      (node (ref "TR6") (pin "1") (pinfunction "D_1") (pintype "passive"))
    )
    (net (code "65") (name "Net-(TR7-D)") (class "Default")
      (node (ref "R11") (pin "1") (pinfunction "1_1") (pintype "bidirectional"))
      (node (ref "TR7") (pin "1") (pinfunction "D_1") (pintype "passive"))
    )
    (net (code "66") (name "Net-(TR8-D)") (class "Default")
      (node (ref "R12") (pin "1") (pinfunction "1_1") (pintype "bidirectional"))
      (node (ref "TR8") (pin "1") (pinfunction "D_1") (pintype "passive"))
    )
    (net (code "67") (name "Net-(TR9-D)") (class "Default")
      (node (ref "R13") (pin "1") (pinfunction "1_1") (pintype "bidirectional"))
      (node (ref "TR9") (pin "1") (pinfunction "D_1") (pintype "passive"))
    )
    (net (code "68") (name "Net-(TR10-D)") (class "Default")
      (node (ref "R14") (pin "1") (pinfunction "1_1") (pintype "bidirectional"))
      (node (ref "TR10") (pin "1") (pinfunction "D_1") (pintype "passive"))
    )
    (net (code "69") (name "Net-(TR11-D)") (class "Default")
      (node (ref "R16") (pin "1") (pinfunction "1_1") (pintype "bidirectional"))
      (node (ref "TR11") (pin "1") (pinfunction "D_1") (pintype "passive"))
    )
    (net (code "70") (name "Net-(TR12-D)") (class "Default")
      (node (ref "R17") (pin "1") (pinfunction "1_1") (pintype "bidirectional"))
      (node (ref "TR12") (pin "1") (pinfunction "D_1") (pintype "passive"))
    )
    (net (code "71") (name "Net-(TR13-D)") (class "Default")
      (node (ref "R18") (pin "1") (pinfunction "1_1") (pintype "bidirectional"))
      (node (ref "TR13") (pin "1") (pinfunction "D_1") (pintype "passive"))
    )
    (net (code "72") (name "Net-(TR14-D)") (class "Default")
      (node (ref "R19") (pin "1") (pinfunction "1_1") (pintype "bidirectional"))
      (node (ref "TR14") (pin "1") (pinfunction "D_1") (pintype "passive"))
    )
    (net (code "73") (name "Net-(TR15-D)") (class "Default")
      (node (ref "R20") (pin "1") (pinfunction "1_1") (pintype "bidirectional"))
      (node (ref "TR15") (pin "1") (pinfunction "D_1") (pintype "passive"))
    )
    (net (code "74") (name "Net-(TR16-D)") (class "Default")
      (node (ref "R21") (pin "1") (pinfunction "1_1") (pintype "bidirectional"))
      (node (ref "TR16") (pin "1") (pinfunction "D_1") (pintype "passive"))
    )
    (net (code "75") (name "SCK") (class "Default")
      (node (ref "IC2") (pin "26") (pinfunction "PA17/I2C/EIC/SCOM1PAD1+/TC2_26") (pintype "bidirectional"))
      (node (ref "SPI") (pin "5") (pinfunction "SCK_5") (pintype "bidirectional"))
    )
    (net (code "76") (name "SS") (class "Default")
      (node (ref "IC2") (pin "27") (pinfunction "PA18/EIC/SCOM1PAD2+/TC3_27") (pintype "bidirectional"))
      (node (ref "SPI") (pin "3") (pinfunction "CS_3") (pintype "bidirectional"))
    )
    (net (code "77") (name "TARGET_RESET") (class "Default")
      (node (ref "C8") (pin "1") (pinfunction "1_1") (pintype "passive"))
      (node (ref "IC2") (pin "40") (pinfunction "RESETN_40") (pintype "bidirectional"))
      (node (ref "R2") (pin "2") (pinfunction "2_2") (pintype "bidirectional"))
    )
    (net (code "78") (name "unconnected-(CN1-Pad6)") (class "Default")
      (node (ref "CN1") (pin "6") (pinfunction "6_6") (pintype "bidirectional"))
    )
    (net (code "79") (name "unconnected-(CN1-Pad7)") (class "Default")
      (node (ref "CN1") (pin "7") (pinfunction "7_7") (pintype "bidirectional"))
    )
    (net (code "80") (name "unconnected-(CN1-Pad8)") (class "Default")
      (node (ref "CN1") (pin "8") (pinfunction "8_8") (pintype "bidirectional"))
    )
    (net (code "81") (name "unconnected-(SPI-NC-Pad4)") (class "Default")
      (node (ref "SPI") (pin "4") (pinfunction "NC_4") (pintype "bidirectional"))
    )
    (net (code "82") (name "unconnected-(TR14-G-Pad3)") (class "Default")
      (node (ref "TR14") (pin "3") (pinfunction "G_3") (pintype "passive"))
    )
    (net (code "83") (name "unconnected-(TR15-G-Pad3)") (class "Default")
      (node (ref "TR15") (pin "3") (pinfunction "G_3") (pintype "passive"))
    )
    (net (code "84") (name "unconnected-(TR16-G-Pad3)") (class "Default")
      (node (ref "TR16") (pin "3") (pinfunction "G_3") (pintype "passive"))
    )
  )
)
